# Sensor_inputs.net
KiCad netlist of a schematic drawn in Altium Designer
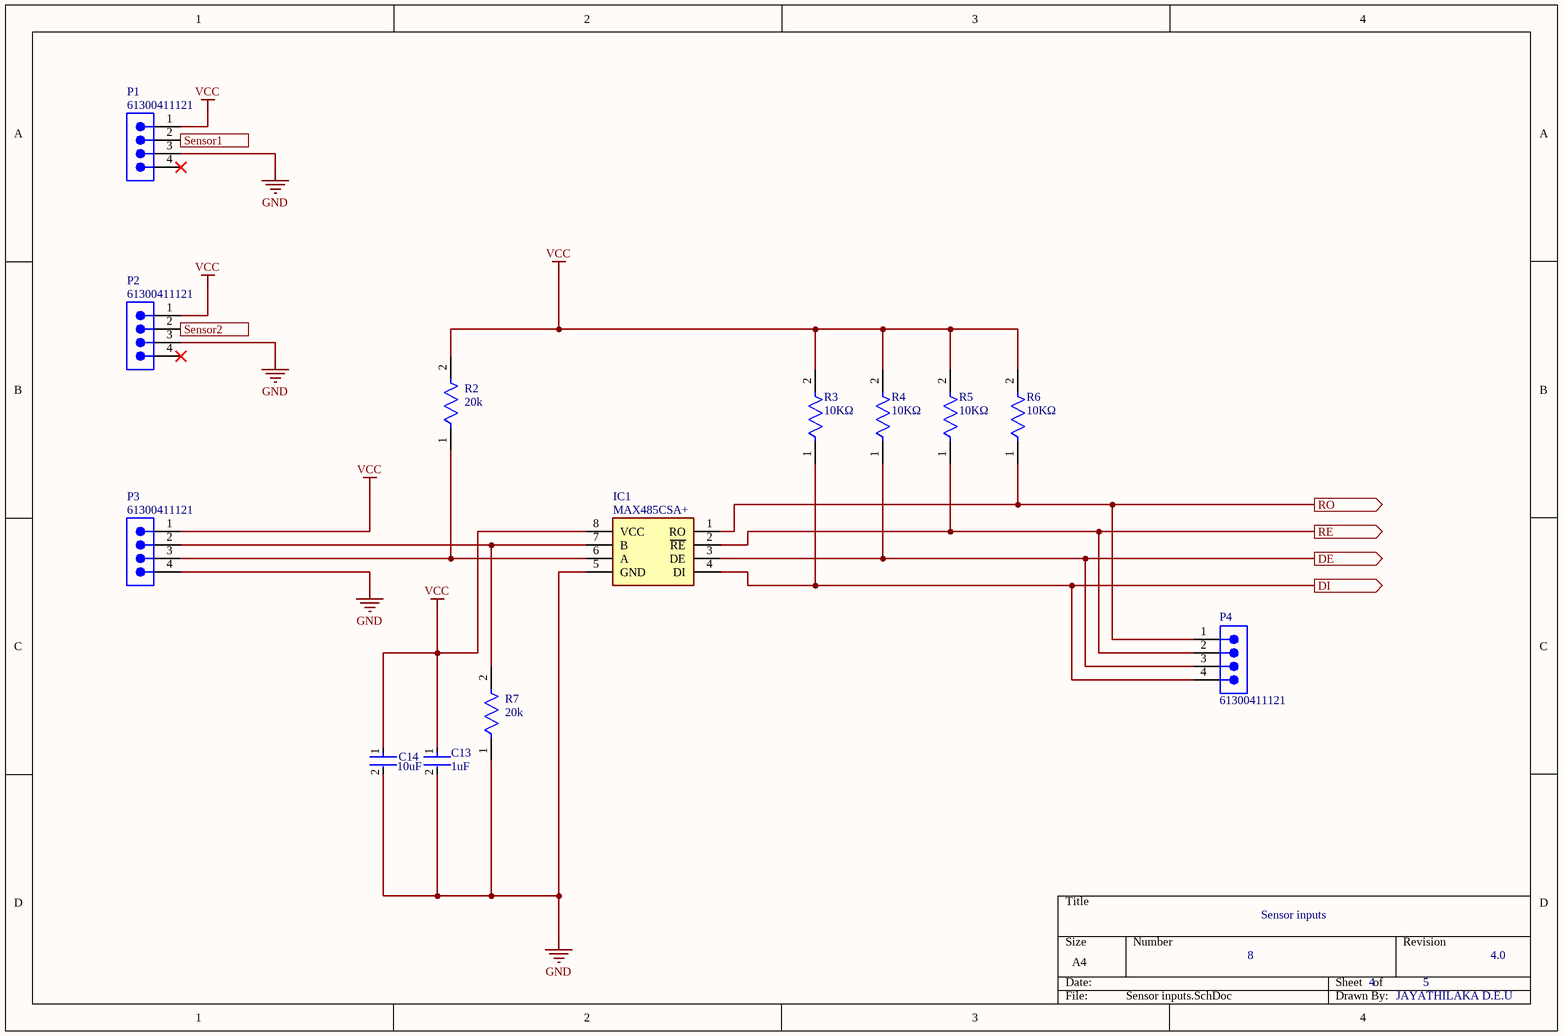
[diagram p0: Sensor inputs.SchDoc]

(export (version "E")
  (design (tool "Eeschema 10.0.6"))
  (components
    (comp (ref "C13")
      (value "12061C105K4T2A")
      (footprint "FP-1206-L_3_2_0_2-W_1_6_0-IPC_A")
      (description "Automotive Ceramic Capacitor, 1206, 1uF, 10%, X7R, 15%,")
      (fields (field (name "CAPACITANCE") "1uF") (field (name "TOLERANCE") "10%"))
      (libsource (lib "Altium Content Vault") (part "b4654b650e69147ec39a6b967a45e02"))
    )
    (comp (ref "C14")
      (value "10uF")
      (footprint "FP-CL31B106KBHNNNE-MFG")
      (description "CAP CER 10UF 50V X7R 1206")
      (fields (field (name "MANUFACTURER") "Samsung") (field (name "TOLERANCE") "10%"))
      (libsource (lib "Altium Content Vault") (part "b4654b650e69147ec39a6b967a45e02"))
    )
    (comp (ref "IC1")
      (value "MAX485CSA+")
      (footprint "SamacSys:SOIC127P600X175-8N")
      (description "Integrated Circuit")
      (fields (field (name "MOUSER PART NUMBER") "700-MAX485CSA"))
      (libsource (lib "*") (part "MAX485CSA+"))
    )
    (comp (ref "P1")
      (value "61300411121")
      (footprint "61300411121")
      (libsource (lib "Altium Content Vault") (part "Header_Male_1R_04P"))
    )
    (comp (ref "P2")
      (value "61300411121")
      (footprint "61300411121")
      (libsource (lib "Altium Content Vault") (part "Header_Male_1R_04P"))
    )
    (comp (ref "P3")
      (value "61300411121")
      (footprint "61300411121")
      (libsource (lib "Altium Content Vault") (part "Header_Male_1R_04P"))
    )
    (comp (ref "P4")
      (value "61300411121")
      (footprint "61300411121")
      (libsource (lib "Altium Content Vault") (part "Header_Male_1R_04P"))
    )
    (comp (ref "R2")
      (value "ERA8AEB203V")
      (footprint "FP-ERA8A-IPC_A")
      (description "RES SMD 20K OHM 0.1% 1/4W 1206")
      (fields (field (name "RESISTANCE") "20k") (field (name "TOLERANCE") "0.1%"))
      (libsource (lib "Altium Content Vault") (part "1029c3af85768c4190bb7ad29bc67b5"))
    )
    (comp (ref "R3")
      (value "RT1206BRD0710KL")
      (footprint "FP-RT1206-MFG")
      (description "RES 10.0K OHM 1/4W .1% SMD 1206")
      (fields
        (field (name "OCTOPART") "https://octopart.com/rt1206brd0710kl-yageo-1397513")
        (field (name "RESISTANCE") "10KΩ")
        (field (name "MANUFACTURER") "Yageo")
      )
      (libsource (lib "Altium Content Vault") (part "1029c3af85768c4190bb7ad29bc67b5"))
    )
    (comp (ref "R4")
      (value "RT1206BRD0710KL")
      (footprint "FP-RT1206-MFG")
      (description "RES 10.0K OHM 1/4W .1% SMD 1206")
      (fields
        (field (name "OCTOPART") "https://octopart.com/rt1206brd0710kl-yageo-1397513")
        (field (name "RESISTANCE") "10KΩ")
        (field (name "MANUFACTURER") "Yageo")
      )
      (libsource (lib "Altium Content Vault") (part "1029c3af85768c4190bb7ad29bc67b5"))
    )
    (comp (ref "R5")
      (value "RT1206BRD0710KL")
      (footprint "FP-RT1206-MFG")
      (description "RES 10.0K OHM 1/4W .1% SMD 1206")
      (fields
        (field (name "OCTOPART") "https://octopart.com/rt1206brd0710kl-yageo-1397513")
        (field (name "RESISTANCE") "10KΩ")
        (field (name "MANUFACTURER") "Yageo")
      )
      (libsource (lib "Altium Content Vault") (part "1029c3af85768c4190bb7ad29bc67b5"))
    )
    (comp (ref "R6")
      (value "RT1206BRD0710KL")
      (footprint "FP-RT1206-MFG")
      (description "RES 10.0K OHM 1/4W .1% SMD 1206")
      (fields
        (field (name "OCTOPART") "https://octopart.com/rt1206brd0710kl-yageo-1397513")
        (field (name "RESISTANCE") "10KΩ")
        (field (name "MANUFACTURER") "Yageo")
      )
      (libsource (lib "Altium Content Vault") (part "1029c3af85768c4190bb7ad29bc67b5"))
    )
    (comp (ref "R7")
      (value "ERA8AEB203V")
      (footprint "FP-ERA8A-IPC_A")
      (description "RES SMD 20K OHM 0.1% 1/4W 1206")
      (fields (field (name "RESISTANCE") "20k") (field (name "TOLERANCE") "0.1%"))
      (libsource (lib "Altium Content Vault") (part "1029c3af85768c4190bb7ad29bc67b5"))
    )
  )
  (nets
    (net (code "1") (name "/DE") (class "Default")
      (node (ref "IC1") (pin "3") (pinfunction "DE_3") (pintype "passive"))
      (node (ref "P4") (pin "3") (pinfunction "3_3") (pintype "passive"))
      (node (ref "R4") (pin "1") (pinfunction "1_1") (pintype "passive"))
    )
    (net (code "2") (name "/DI") (class "Default")
      (node (ref "IC1") (pin "4") (pinfunction "DI_4") (pintype "passive"))
      (node (ref "P4") (pin "4") (pinfunction "4_4") (pintype "passive"))
      (node (ref "R3") (pin "1") (pinfunction "1_1") (pintype "passive"))
    )
    (net (code "3") (name "/RE") (class "Default")
      (node (ref "IC1") (pin "2") (pinfunction "~{RE}_2") (pintype "passive"))
      (node (ref "P4") (pin "2") (pinfunction "2_2") (pintype "passive"))
      (node (ref "R5") (pin "1") (pinfunction "1_1") (pintype "passive"))
    )
    (net (code "4") (name "/RO") (class "Default")
      (node (ref "IC1") (pin "1") (pinfunction "RO_1") (pintype "passive"))
      (node (ref "P4") (pin "1") (pinfunction "1_1") (pintype "passive"))
      (node (ref "R6") (pin "1") (pinfunction "1_1") (pintype "passive"))
    )
    (net (code "5") (name "/Sensor1") (class "Default")
      (node (ref "P1") (pin "2") (pinfunction "2_2") (pintype "passive"))
    )
    (net (code "6") (name "/Sensor2") (class "Default")
      (node (ref "P2") (pin "2") (pinfunction "2_2") (pintype "passive"))
    )
    (net (code "7") (name "GND") (class "Default")
      (node (ref "C13") (pin "2") (pinfunction "2_2") (pintype "passive"))
      (node (ref "C14") (pin "2") (pinfunction "2_2") (pintype "passive"))
      (node (ref "IC1") (pin "5") (pinfunction "GND_5") (pintype "passive"))
      (node (ref "P1") (pin "3") (pinfunction "3_3") (pintype "passive"))
      (node (ref "P2") (pin "3") (pinfunction "3_3") (pintype "passive"))
      (node (ref "P3") (pin "4") (pinfunction "4_4") (pintype "passive"))
      (node (ref "R7") (pin "1") (pinfunction "1_1") (pintype "passive"))
    )
    (net (code "8") (name "Net-(IC1-A)") (class "Default")
      (node (ref "IC1") (pin "6") (pinfunction "A_6") (pintype "passive"))
      (node (ref "P3") (pin "3") (pinfunction "3_3") (pintype "passive"))
      (node (ref "R2") (pin "1") (pinfunction "1_1") (pintype "passive"))
    )
    (net (code "9") (name "Net-(IC1-B)") (class "Default")
      (node (ref "IC1") (pin "7") (pinfunction "B_7") (pintype "passive"))
      (node (ref "P3") (pin "2") (pinfunction "2_2") (pintype "passive"))
      (node (ref "R7") (pin "2") (pinfunction "2_2") (pintype "passive"))
    )
    (net (code "10") (name "VCC") (class "Default")
      (node (ref "C13") (pin "1") (pinfunction "1_1") (pintype "passive"))
      (node (ref "C14") (pin "1") (pinfunction "1_1") (pintype "passive"))
      (node (ref "IC1") (pin "8") (pinfunction "VCC_8") (pintype "passive"))
      (node (ref "P1") (pin "1") (pinfunction "1_1") (pintype "passive"))
      (node (ref "P2") (pin "1") (pinfunction "1_1") (pintype "passive"))
      (node (ref "P3") (pin "1") (pinfunction "1_1") (pintype "passive"))
      (node (ref "R2") (pin "2") (pinfunction "2_2") (pintype "passive"))
      (node (ref "R3") (pin "2") (pinfunction "2_2") (pintype "passive"))
      (node (ref "R4") (pin "2") (pinfunction "2_2") (pintype "passive"))
      (node (ref "R5") (pin "2") (pinfunction "2_2") (pintype "passive"))
      (node (ref "R6") (pin "2") (pinfunction "2_2") (pintype "passive"))
    )
    (net (code "11") (name "unconnected-(P1-Pad4)") (class "Default")
      (node (ref "P1") (pin "4") (pinfunction "4_4") (pintype "passive+no_connect"))
    )
    (net (code "12") (name "unconnected-(P2-Pad4)") (class "Default")
      (node (ref "P2") (pin "4") (pinfunction "4_4") (pintype "passive+no_connect"))
    )
  )
)
